# USB-UART_FT230XS_single-sided.net
KiCad netlist of a schematic drawn in EAGLE
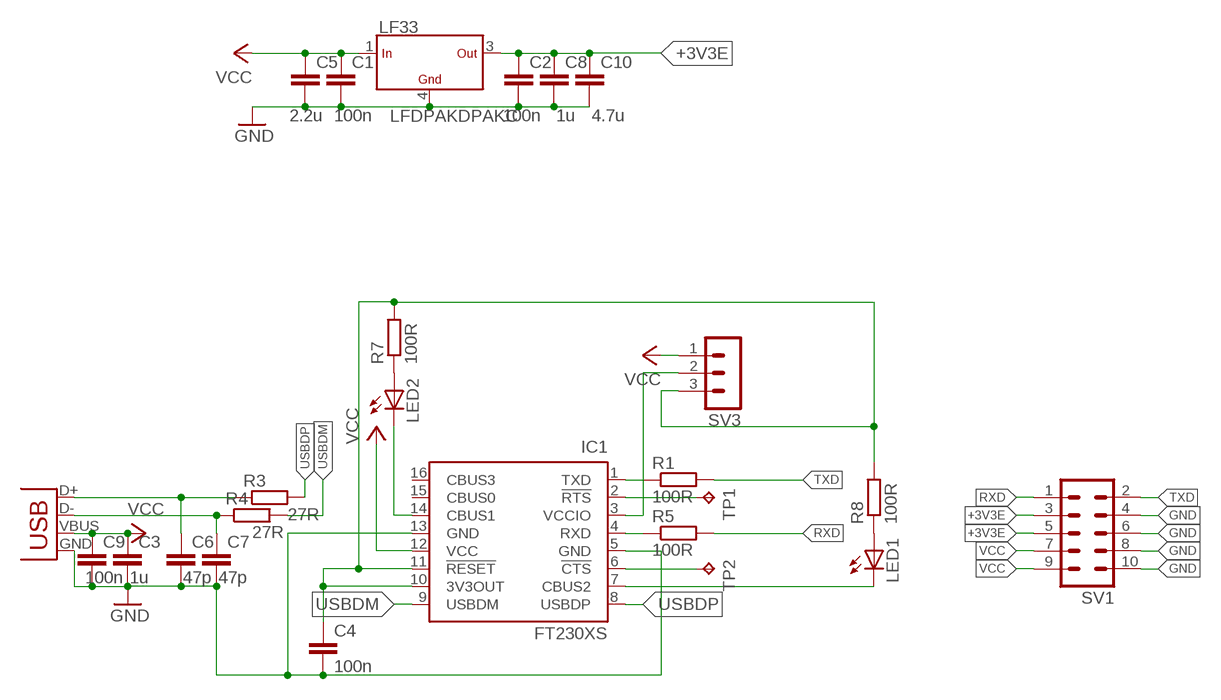
[diagram p0: schematic, sheet 1]

(export (version "E")
  (design (tool "Eeschema 10.0.6"))
  (components
    (comp (ref "C1")
      (value "100n")
      (footprint "eagle-import:C0805")
      (libsource (lib "eagle-import") (part "C-EUC0805"))
    )
    (comp (ref "C2")
      (value "100n")
      (footprint "eagle-import:C0805")
      (libsource (lib "eagle-import") (part "C-EUC0805"))
    )
    (comp (ref "C3")
      (value "1u")
      (footprint "eagle-import:C0805")
      (libsource (lib "eagle-import") (part "C-EUC0805"))
    )
    (comp (ref "C4")
      (value "100n")
      (footprint "eagle-import:C0805")
      (libsource (lib "eagle-import") (part "C-EUC0805"))
    )
    (comp (ref "C5")
      (value "2.2u")
      (footprint "eagle-import:C1206")
      (libsource (lib "eagle-import") (part "C-EUC1206"))
    )
    (comp (ref "C6")
      (value "47p")
      (footprint "eagle-import:C0805")
      (libsource (lib "eagle-import") (part "C-EUC0805"))
    )
    (comp (ref "C7")
      (value "47p")
      (footprint "eagle-import:C0805")
      (libsource (lib "eagle-import") (part "C-EUC0805"))
    )
    (comp (ref "C8")
      (value "1u")
      (footprint "eagle-import:C1206")
      (libsource (lib "eagle-import") (part "C-EUC1206"))
    )
    (comp (ref "C9")
      (value "100n")
      (footprint "eagle-import:C1206")
      (libsource (lib "eagle-import") (part "C-EUC1206"))
    )
    (comp (ref "C10")
      (value "4.7u")
      (footprint "eagle-import:C1206")
      (libsource (lib "eagle-import") (part "C-EUC1206"))
    )
    (comp (ref "IC1")
      (value "FT230XS")
      (footprint "eagle-import:SSOP16")
      (libsource (lib "eagle-import") (part "FT230XS"))
    )
    (comp (ref "LED1")
      (value "LEDCHIP-LED0603")
      (footprint "eagle-import:CHIP-LED0603")
      (libsource (lib "eagle-import") (part "LEDCHIP-LED0603"))
    )
    (comp (ref "LED2")
      (value "LEDCHIP-LED0603")
      (footprint "eagle-import:CHIP-LED0603")
      (libsource (lib "eagle-import") (part "LEDCHIP-LED0603"))
    )
    (comp (ref "LF33")
      (value "LFDPAKDPAKC")
      (footprint "eagle-import:DPAK")
      (libsource (lib "eagle-import") (part "LF??CDPAK"))
    )
    (comp (ref "R1")
      (value "100R")
      (footprint "eagle-import:M0805")
      (libsource (lib "eagle-import") (part "R-EU_M0805"))
    )
    (comp (ref "R3")
      (value "27R")
      (footprint "eagle-import:M0805")
      (libsource (lib "eagle-import") (part "R-EU_M0805"))
    )
    (comp (ref "R4")
      (value "27R")
      (footprint "eagle-import:M0805")
      (libsource (lib "eagle-import") (part "R-EU_M0805"))
    )
    (comp (ref "R5")
      (value "100R")
      (footprint "eagle-import:M0805")
      (libsource (lib "eagle-import") (part "R-EU_M0805"))
    )
    (comp (ref "R7")
      (value "100R")
      (footprint "eagle-import:M0805")
      (libsource (lib "eagle-import") (part "R-EU_M0805"))
    )
    (comp (ref "R8")
      (value "100R")
      (footprint "eagle-import:M0805")
      (libsource (lib "eagle-import") (part "R-EU_M0805"))
    )
    (comp (ref "SV1")
      (value "MA05-2")
      (footprint "eagle-import:MA05-2")
      (libsource (lib "eagle-import") (part "MA05-2"))
    )
    (comp (ref "SV3")
      (value "MA03-1")
      (footprint "eagle-import:MA03-1")
      (libsource (lib "eagle-import") (part "MA03-1"))
    )
    (comp (ref "TP1")
      (value "TPB1,27")
      (footprint "eagle-import:B1,27")
      (libsource (lib "eagle-import") (part "TPB1,27"))
    )
    (comp (ref "TP2")
      (value "TPB1,27")
      (footprint "eagle-import:B1,27")
      (libsource (lib "eagle-import") (part "TPB1,27"))
    )
    (comp (ref "X1")
      (value "USBSMD")
      (footprint "eagle-import:USB-MINIB")
      (libsource (lib "eagle-import") (part "USBSMD"))
    )
  )
  (nets
    (net (code "1") (name "+3V3E") (class "Default")
      (node (ref "C10") (pin "1") (pinfunction "1_1") (pintype "passive"))
      (node (ref "C2") (pin "1") (pinfunction "1_1") (pintype "passive"))
      (node (ref "C8") (pin "1") (pinfunction "1_1") (pintype "passive"))
      (node (ref "LF33") (pin "3") (pinfunction "OUT_3") (pintype "passive"))
      (node (ref "SV1") (pin "3") (pinfunction "3_3") (pintype "passive"))
      (node (ref "SV1") (pin "5") (pinfunction "5_5") (pintype "passive"))
    )
    (net (code "2") (name "GND") (class "Default")
      (node (ref "C1") (pin "2") (pinfunction "2_2") (pintype "passive"))
      (node (ref "C10") (pin "2") (pinfunction "2_2") (pintype "passive"))
      (node (ref "C2") (pin "2") (pinfunction "2_2") (pintype "passive"))
      (node (ref "C3") (pin "2") (pinfunction "2_2") (pintype "passive"))
      (node (ref "C4") (pin "2") (pinfunction "2_2") (pintype "passive"))
      (node (ref "C5") (pin "2") (pinfunction "2_2") (pintype "passive"))
      (node (ref "C6") (pin "2") (pinfunction "2_2") (pintype "passive"))
      (node (ref "C7") (pin "2") (pinfunction "2_2") (pintype "passive"))
      (node (ref "C8") (pin "2") (pinfunction "2_2") (pintype "passive"))
      (node (ref "C9") (pin "2") (pinfunction "2_2") (pintype "passive"))
      (node (ref "IC1") (pin "13") (pinfunction "GND_13") (pintype "power_in"))
      (node (ref "IC1") (pin "5") (pinfunction "GND_5") (pintype "power_in"))
      (node (ref "LF33") (pin "4") (pinfunction "GND_4") (pintype "passive"))
      (node (ref "SV1") (pin "10") (pinfunction "10_10") (pintype "passive"))
      (node (ref "SV1") (pin "4") (pinfunction "4_4") (pintype "passive"))
      (node (ref "SV1") (pin "6") (pinfunction "6_6") (pintype "passive"))
      (node (ref "SV1") (pin "8") (pinfunction "8_8") (pintype "passive"))
      (node (ref "X1") (pin "GND") (pinfunction "GND_GND") (pintype "bidirectional"))
    )
    (net (code "3") (name "Net-(C6-Pad1)") (class "Default")
      (node (ref "C6") (pin "1") (pinfunction "1_1") (pintype "passive"))
      (node (ref "R3") (pin "1") (pinfunction "1_1") (pintype "passive"))
      (node (ref "X1") (pin "D+") (pinfunction "D+_D+") (pintype "bidirectional"))
    )
    (net (code "4") (name "Net-(C7-Pad1)") (class "Default")
      (node (ref "C7") (pin "1") (pinfunction "1_1") (pintype "passive"))
      (node (ref "R4") (pin "1") (pinfunction "1_1") (pintype "passive"))
      (node (ref "X1") (pin "D-") (pinfunction "D-_D-") (pintype "bidirectional"))
    )
    (net (code "5") (name "Net-(IC1-3V3OUT)") (class "Default")
      (node (ref "C4") (pin "1") (pinfunction "1_1") (pintype "passive"))
      (node (ref "IC1") (pin "10") (pinfunction "3V3OUT_10") (pintype "output"))
      (node (ref "IC1") (pin "11") (pinfunction "~{RESET}_11") (pintype "input"))
      (node (ref "R7") (pin "2") (pinfunction "2_2") (pintype "passive"))
      (node (ref "R8") (pin "2") (pinfunction "2_2") (pintype "passive"))
      (node (ref "SV3") (pin "3") (pinfunction "3_3") (pintype "passive"))
    )
    (net (code "6") (name "Net-(IC1-CBUS1)") (class "Default")
      (node (ref "IC1") (pin "14") (pinfunction "CBUS1_14") (pintype "bidirectional"))
      (node (ref "LED2") (pin "C") (pinfunction "C_C") (pintype "passive"))
    )
    (net (code "7") (name "Net-(IC1-CBUS2)") (class "Default")
      (node (ref "IC1") (pin "7") (pinfunction "CBUS2_7") (pintype "bidirectional"))
      (node (ref "LED1") (pin "C") (pinfunction "C_C") (pintype "passive"))
    )
    (net (code "8") (name "Net-(IC1-RXD)") (class "Default")
      (node (ref "IC1") (pin "4") (pinfunction "RXD_4") (pintype "input"))
      (node (ref "R5") (pin "1") (pinfunction "1_1") (pintype "passive"))
    )
    (net (code "9") (name "Net-(IC1-TXD)") (class "Default")
      (node (ref "IC1") (pin "1") (pinfunction "TXD_1") (pintype "output"))
      (node (ref "R1") (pin "1") (pinfunction "1_1") (pintype "passive"))
    )
    (net (code "10") (name "Net-(IC1-VCCIO)") (class "Default")
      (node (ref "IC1") (pin "3") (pinfunction "VCCIO_3") (pintype "power_in"))
      (node (ref "SV3") (pin "2") (pinfunction "2_2") (pintype "passive"))
    )
    (net (code "11") (name "Net-(IC1-~{CTS})") (class "Default")
      (node (ref "IC1") (pin "6") (pinfunction "~{CTS}_6") (pintype "input"))
      (node (ref "TP2") (pin "TP") (pinfunction "TP_TP") (pintype "input"))
    )
    (net (code "12") (name "Net-(IC1-~{RTS})") (class "Default")
      (node (ref "IC1") (pin "2") (pinfunction "~{RTS}_2") (pintype "output"))
      (node (ref "TP1") (pin "TP") (pinfunction "TP_TP") (pintype "input"))
    )
    (net (code "13") (name "Net-(LED1-PadA)") (class "Default")
      (node (ref "LED1") (pin "A") (pinfunction "A_A") (pintype "passive"))
      (node (ref "R8") (pin "1") (pinfunction "1_1") (pintype "passive"))
    )
    (net (code "14") (name "Net-(LED2-PadA)") (class "Default")
      (node (ref "LED2") (pin "A") (pinfunction "A_A") (pintype "passive"))
      (node (ref "R7") (pin "1") (pinfunction "1_1") (pintype "passive"))
    )
    (net (code "15") (name "RXD") (class "Default")
      (node (ref "R5") (pin "2") (pinfunction "2_2") (pintype "passive"))
      (node (ref "SV1") (pin "1") (pinfunction "1_1") (pintype "passive"))
    )
    (net (code "16") (name "TXD") (class "Default")
      (node (ref "R1") (pin "2") (pinfunction "2_2") (pintype "passive"))
      (node (ref "SV1") (pin "2") (pinfunction "2_2") (pintype "passive"))
    )
    (net (code "17") (name "USBDM") (class "Default")
      (node (ref "IC1") (pin "9") (pinfunction "USBDM_9") (pintype "input"))
      (node (ref "R4") (pin "2") (pinfunction "2_2") (pintype "passive"))
    )
    (net (code "18") (name "USBDP") (class "Default")
      (node (ref "IC1") (pin "8") (pinfunction "USBDP_8") (pintype "input"))
      (node (ref "R3") (pin "2") (pinfunction "2_2") (pintype "passive"))
    )
    (net (code "19") (name "VCC") (class "Default")
      (node (ref "C1") (pin "1") (pinfunction "1_1") (pintype "passive"))
      (node (ref "C3") (pin "1") (pinfunction "1_1") (pintype "passive"))
      (node (ref "C5") (pin "1") (pinfunction "1_1") (pintype "passive"))
      (node (ref "C9") (pin "1") (pinfunction "1_1") (pintype "passive"))
      (node (ref "IC1") (pin "12") (pinfunction "VCC_12") (pintype "power_in"))
      (node (ref "LF33") (pin "1") (pinfunction "IN_1") (pintype "passive"))
      (node (ref "SV1") (pin "7") (pinfunction "7_7") (pintype "passive"))
      (node (ref "SV1") (pin "9") (pinfunction "9_9") (pintype "passive"))
      (node (ref "SV3") (pin "1") (pinfunction "1_1") (pintype "passive"))
      (node (ref "X1") (pin "VBUS") (pinfunction "VBUS_VBUS") (pintype "bidirectional"))
    )
    (net (code "20") (name "unconnected-(IC1-CBUS0-Pad15)") (class "Default")
      (node (ref "IC1") (pin "15") (pinfunction "CBUS0_15") (pintype "bidirectional"))
    )
    (net (code "21") (name "unconnected-(IC1-CBUS3-Pad16)") (class "Default")
      (node (ref "IC1") (pin "16") (pinfunction "CBUS3_16") (pintype "bidirectional"))
    )
  )
)
